# bike-blinky.net
KiCad netlist of a schematic drawn in EAGLE
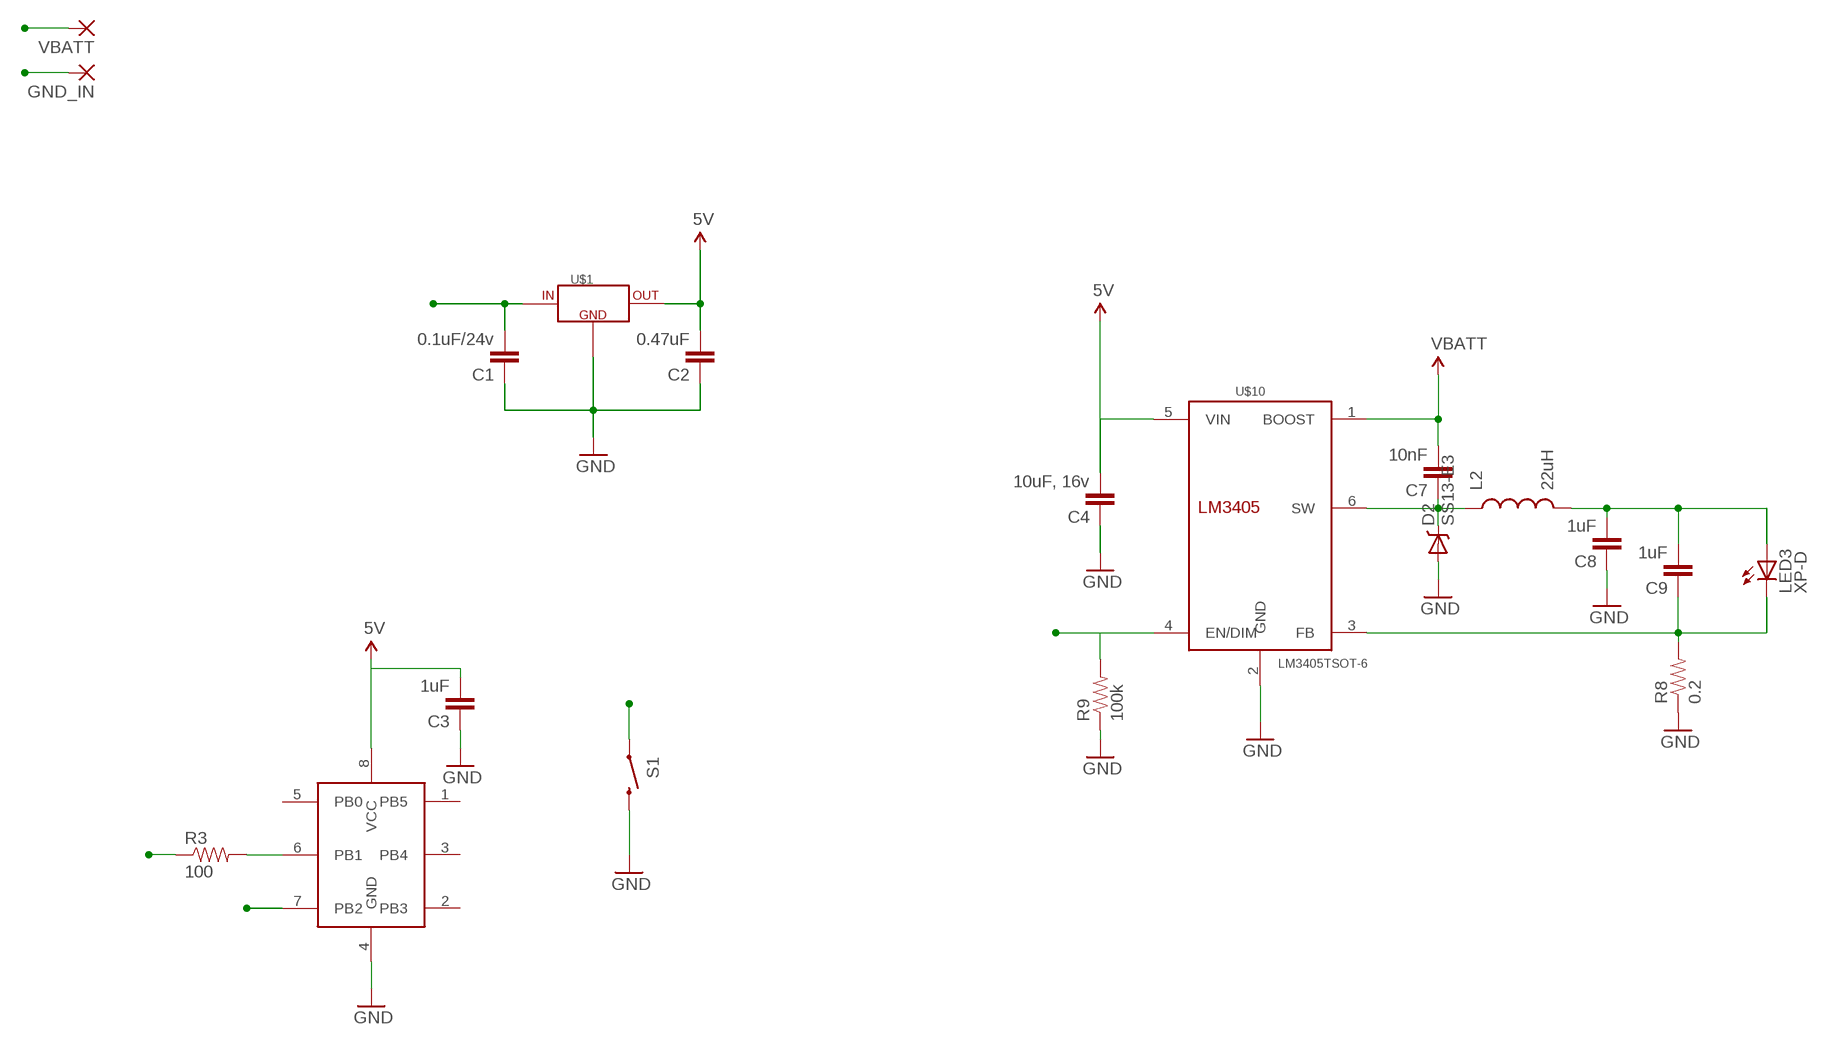
[diagram p0: schematic, sheet 1]

(export (version "E")
  (design (tool "Eeschema 10.0.6"))
  (components
    (comp (ref "C1")
      (value "0.1uF/24v")
      (footprint "eagle-import:0603-CAP")
      (libsource (lib "eagle-import") (part "CAP0603-CAP"))
    )
    (comp (ref "C2")
      (value "0.47uF")
      (footprint "eagle-import:0603-CAP")
      (libsource (lib "eagle-import") (part "CAP0603-CAP"))
    )
    (comp (ref "C3")
      (value "1uF")
      (footprint "eagle-import:0603-CAP")
      (libsource (lib "eagle-import") (part "CAP0603-CAP"))
    )
    (comp (ref "C4")
      (value "10uF, 16v")
      (footprint "eagle-import:1206")
      (libsource (lib "eagle-import") (part "CAP1206"))
    )
    (comp (ref "C7")
      (value "10nF")
      (footprint "eagle-import:1206")
      (libsource (lib "eagle-import") (part "SparkFun-Capacitors_CAP1206"))
    )
    (comp (ref "C8")
      (value "1uF")
      (footprint "eagle-import:1206")
      (libsource (lib "eagle-import") (part "SparkFun-Capacitors_CAP1206"))
    )
    (comp (ref "C9")
      (value "1uF")
      (footprint "eagle-import:1206")
      (libsource (lib "eagle-import") (part "SparkFun-Capacitors_CAP1206"))
    )
    (comp (ref "D2")
      (value "SS13-E3")
      (footprint "eagle-import:SMA-DIODE")
      (libsource (lib "eagle-import") (part "MBRA140"))
    )
    (comp (ref "GND_IN")
      (value "WIREPAD2,54/1,0")
      (footprint "eagle-import:2,54_1,0")
      (libsource (lib "eagle-import") (part "WIREPAD2,54/1,0"))
    )
    (comp (ref "L2")
      (value "22uH")
      (footprint "eagle-import:1210")
      (libsource (lib "eagle-import") (part "INDUCTOR1210"))
    )
    (comp (ref "LED3")
      (value "XP-D")
      (footprint "eagle-import:XB-D-REV1")
      (libsource (lib "eagle-import") (part "XLAMP-XB-D-LED"))
    )
    (comp (ref "R3")
      (value "100")
      (footprint "eagle-import:0603-RES")
      (libsource (lib "eagle-import") (part "RESISTOR0603-RES"))
    )
    (comp (ref "R8")
      (value "0.2")
      (footprint "eagle-import:R2010")
      (libsource (lib "eagle-import") (part "SparkFun-Passives_RESISTOR2010"))
    )
    (comp (ref "R9")
      (value "100k")
      (footprint "eagle-import:0603-RES")
      (libsource (lib "eagle-import") (part "SparkFun-Passives_RESISTOR0603-RES"))
    )
    (comp (ref "S1")
      (value "SWITCH-MOMENTARY-2SMD-2")
      (footprint "eagle-import:TACTILE_SWITCH_SMD-2")
      (libsource (lib "eagle-import") (part "SWITCH-MOMENTARY-2SMD-2"))
    )
    (comp (ref "U$1")
      (value "TPS715XX")
      (footprint "eagle-import:SC70-5")
      (libsource (lib "eagle-import") (part "TPS715XX"))
    )
    (comp (ref "U$2")
      (value "ATTINY13")
      (footprint "eagle-import:WSOIC-8")
      (libsource (lib "eagle-import") (part "ATTINY13"))
    )
    (comp (ref "U$10")
      (value "LM3405TSOT-6")
      (footprint "eagle-import:TSOT-6")
      (libsource (lib "eagle-import") (part "LM3405TSOT-6"))
    )
    (comp (ref "VBATT")
      (value "WIREPAD2,54/1,0")
      (footprint "eagle-import:2,54_1,0")
      (libsource (lib "eagle-import") (part "WIREPAD2,54/1,0"))
    )
  )
  (nets
    (net (code "1") (name "/RED") (class "Default")
      (node (ref "R3") (pin "1") (pinfunction "1_1") (pintype "passive"))
      (node (ref "R9") (pin "2") (pinfunction "2_2") (pintype "passive"))
      (node (ref "U$10") (pin "4") (pinfunction "EN/DIM_4") (pintype "bidirectional"))
    )
    (net (code "2") (name "/SW") (class "Default")
      (node (ref "S1") (pin "2") (pinfunction "1_2") (pintype "passive"))
      (node (ref "U$2") (pin "7") (pinfunction "PB2_7") (pintype "bidirectional"))
    )
    (net (code "3") (name "5V") (class "Default")
      (node (ref "C2") (pin "2") (pinfunction "2_2") (pintype "passive"))
      (node (ref "C3") (pin "2") (pinfunction "2_2") (pintype "passive"))
      (node (ref "C4") (pin "2") (pinfunction "2_2") (pintype "passive"))
      (node (ref "U$1") (pin "5") (pinfunction "OUT_5") (pintype "bidirectional"))
      (node (ref "U$10") (pin "5") (pinfunction "VIN_5") (pintype "bidirectional"))
      (node (ref "U$2") (pin "8") (pinfunction "VCC_8") (pintype "bidirectional"))
    )
    (net (code "4") (name "GND") (class "Default")
      (node (ref "C1") (pin "1") (pinfunction "1_1") (pintype "passive"))
      (node (ref "C2") (pin "1") (pinfunction "1_1") (pintype "passive"))
      (node (ref "C3") (pin "1") (pinfunction "1_1") (pintype "passive"))
      (node (ref "C4") (pin "1") (pinfunction "1_1") (pintype "passive"))
      (node (ref "C8") (pin "1") (pinfunction "1_1") (pintype "passive"))
      (node (ref "D2") (pin "A") (pinfunction "A_A") (pintype "passive"))
      (node (ref "GND_IN") (pin "1") (pinfunction "P_1") (pintype "passive"))
      (node (ref "R8") (pin "1") (pinfunction "1_1") (pintype "passive"))
      (node (ref "R9") (pin "1") (pinfunction "1_1") (pintype "passive"))
      (node (ref "S1") (pin "1") (pinfunction "2_1") (pintype "passive"))
      (node (ref "U$1") (pin "2") (pinfunction "GND_2") (pintype "bidirectional"))
      (node (ref "U$10") (pin "2") (pinfunction "GND_2") (pintype "bidirectional"))
      (node (ref "U$2") (pin "4") (pinfunction "GND_4") (pintype "bidirectional"))
    )
    (net (code "5") (name "Net-(C8-Pad2)") (class "Default")
      (node (ref "C8") (pin "2") (pinfunction "2_2") (pintype "passive"))
      (node (ref "C9") (pin "2") (pinfunction "2_2") (pintype "passive"))
      (node (ref "L2") (pin "2") (pinfunction "2_2") (pintype "passive"))
      (node (ref "LED3") (pin "A") (pinfunction "A_A") (pintype "passive"))
    )
    (net (code "6") (name "Net-(U$2-PB1)") (class "Default")
      (node (ref "R3") (pin "2") (pinfunction "2_2") (pintype "passive"))
      (node (ref "U$2") (pin "6") (pinfunction "PB1_6") (pintype "bidirectional"))
    )
    (net (code "7") (name "Net-(U$10-FB)") (class "Default")
      (node (ref "C9") (pin "1") (pinfunction "1_1") (pintype "passive"))
      (node (ref "LED3") (pin "C") (pinfunction "C_C") (pintype "passive"))
      (node (ref "R8") (pin "2") (pinfunction "2_2") (pintype "passive"))
      (node (ref "U$10") (pin "3") (pinfunction "FB_3") (pintype "bidirectional"))
    )
    (net (code "8") (name "Net-(U$10-SW)") (class "Default")
      (node (ref "C7") (pin "1") (pinfunction "1_1") (pintype "passive"))
      (node (ref "D2") (pin "C") (pinfunction "C_C") (pintype "passive"))
      (node (ref "L2") (pin "1") (pinfunction "1_1") (pintype "passive"))
      (node (ref "U$10") (pin "6") (pinfunction "SW_6") (pintype "bidirectional"))
    )
    (net (code "9") (name "VBATT") (class "Default")
      (node (ref "C1") (pin "2") (pinfunction "2_2") (pintype "passive"))
      (node (ref "C7") (pin "2") (pinfunction "2_2") (pintype "passive"))
      (node (ref "U$1") (pin "4") (pinfunction "IN_4") (pintype "bidirectional"))
      (node (ref "U$10") (pin "1") (pinfunction "BOOST_1") (pintype "bidirectional"))
      (node (ref "VBATT") (pin "1") (pinfunction "P_1") (pintype "passive"))
    )
    (net (code "10") (name "unconnected-(U$2-PB0-Pad5)") (class "Default")
      (node (ref "U$2") (pin "5") (pinfunction "PB0_5") (pintype "bidirectional"))
    )
    (net (code "11") (name "unconnected-(U$2-PB3-Pad2)") (class "Default")
      (node (ref "U$2") (pin "2") (pinfunction "PB3_2") (pintype "bidirectional"))
    )
    (net (code "12") (name "unconnected-(U$2-PB4-Pad3)") (class "Default")
      (node (ref "U$2") (pin "3") (pinfunction "PB4_3") (pintype "bidirectional"))
    )
    (net (code "13") (name "unconnected-(U$2-PB5-Pad1)") (class "Default")
      (node (ref "U$2") (pin "1") (pinfunction "PB5_1") (pintype "bidirectional"))
    )
  )
)
